# Current_Sensors.net
KiCad netlist of a schematic drawn in Altium Designer
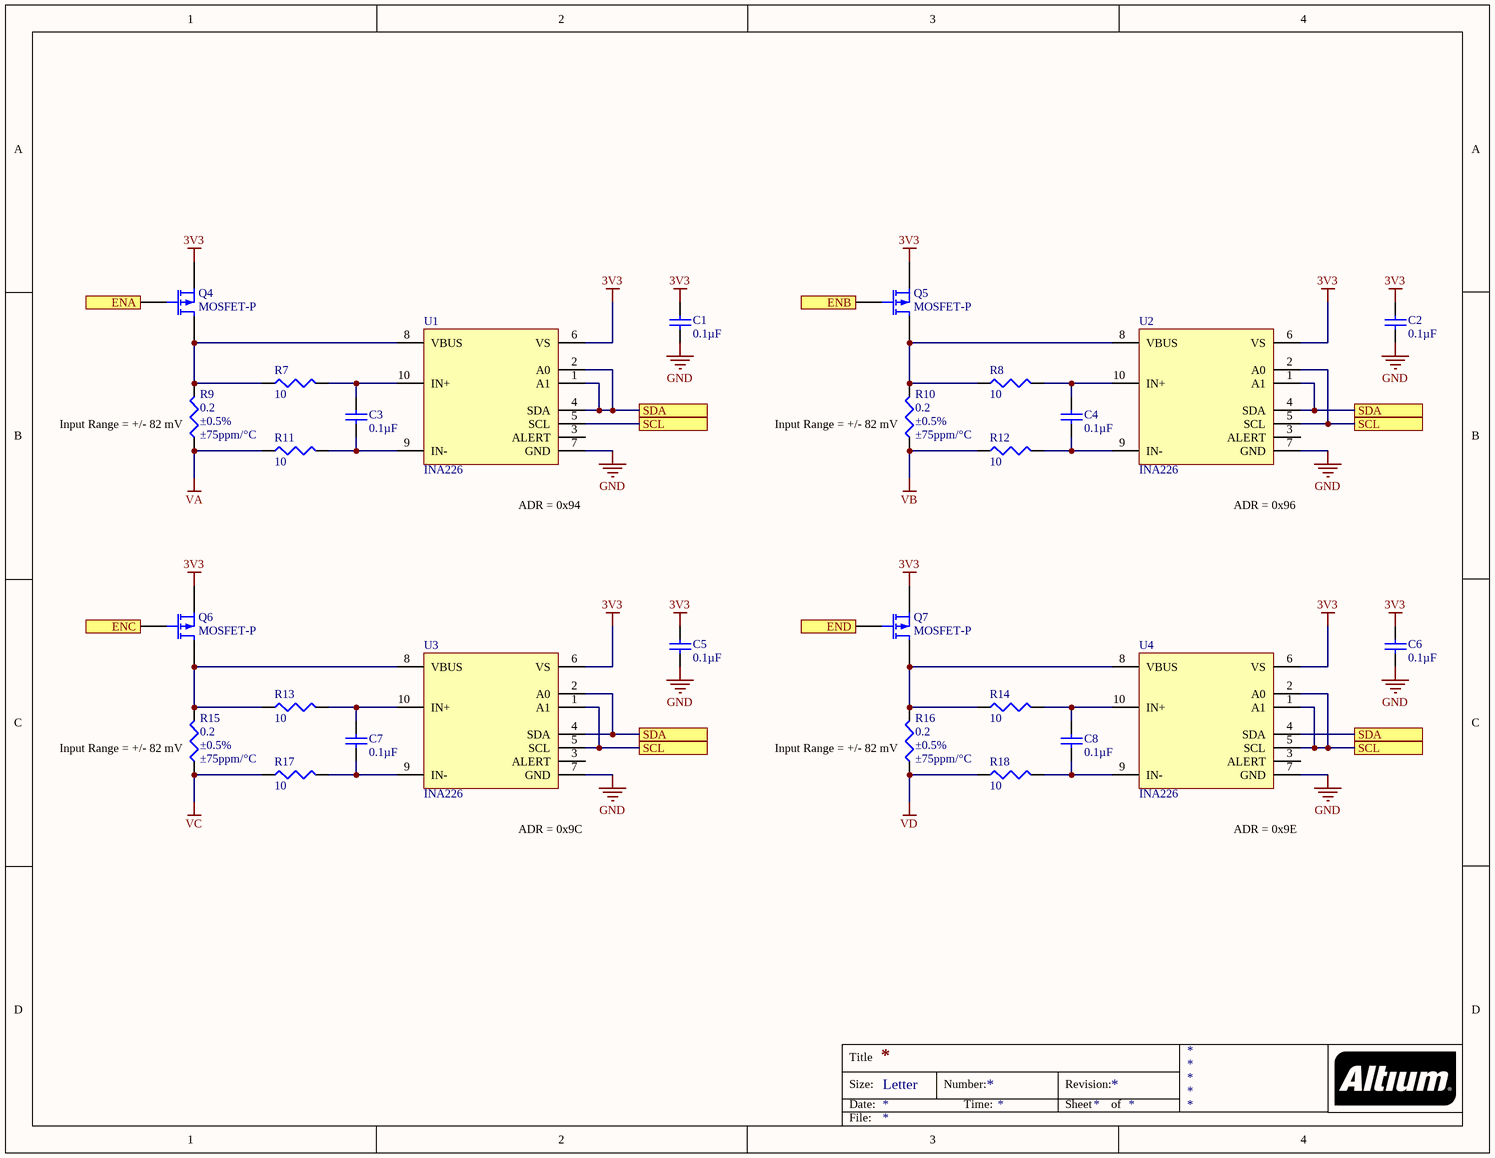
[diagram p0: Current_Sensors.SchDoc]

(export (version "E")
  (design (tool "Eeschema 10.0.6"))
  (components
    (comp (ref "C1")
      (value "0.1µF")
      (footprint "TDK-CGA3E")
      (description "CAP CER 0.1UF 50V X8R 0603")
      (fields
        (field (name "PART NUMBER") "PC-TDK-02273")
        (field (name "MANUFACTURER PART NUMBER") "CGA3E3X8R1H104M080AB")
        (field (name "PUBLISHER") "AlbertaSat")
      )
      (libsource (lib "Database") (part "Cap"))
    )
    (comp (ref "C2")
      (value "0.1µF")
      (footprint "TDK-CGA3E")
      (description "CAP CER 0.1UF 50V X8R 0603")
      (fields
        (field (name "PART NUMBER") "PC-TDK-02273")
        (field (name "MANUFACTURER PART NUMBER") "CGA3E3X8R1H104M080AB")
        (field (name "PUBLISHER") "AlbertaSat")
      )
      (libsource (lib "Database") (part "Cap"))
    )
    (comp (ref "C3")
      (value "0.1µF")
      (footprint "TDK-CGA3E")
      (description "CAP CER 0.1UF 50V X8R 0603")
      (fields
        (field (name "PART NUMBER") "PC-TDK-02272")
        (field (name "MANUFACTURER PART NUMBER") "CGA3E3X8R1H104K080AB")
        (field (name "PUBLISHER") "AlbertaSat")
      )
      (libsource (lib "Database") (part "Cap"))
    )
    (comp (ref "C4")
      (value "0.1µF")
      (footprint "TDK-CGA3E")
      (description "CAP CER 0.1UF 50V X8R 0603")
      (fields
        (field (name "PART NUMBER") "PC-TDK-02272")
        (field (name "MANUFACTURER PART NUMBER") "CGA3E3X8R1H104K080AB")
        (field (name "PUBLISHER") "AlbertaSat")
      )
      (libsource (lib "Database") (part "Cap"))
    )
    (comp (ref "C5")
      (value "0.1µF")
      (footprint "TDK-CGA3E")
      (description "CAP CER 0.1UF 50V X8R 0603")
      (fields
        (field (name "PART NUMBER") "PC-TDK-02273")
        (field (name "MANUFACTURER PART NUMBER") "CGA3E3X8R1H104M080AB")
        (field (name "PUBLISHER") "AlbertaSat")
      )
      (libsource (lib "Database") (part "Cap"))
    )
    (comp (ref "C6")
      (value "0.1µF")
      (footprint "TDK-CGA3E")
      (description "CAP CER 0.1UF 50V X8R 0603")
      (fields
        (field (name "PART NUMBER") "PC-TDK-02273")
        (field (name "MANUFACTURER PART NUMBER") "CGA3E3X8R1H104M080AB")
        (field (name "PUBLISHER") "AlbertaSat")
      )
      (libsource (lib "Database") (part "Cap"))
    )
    (comp (ref "C7")
      (value "0.1µF")
      (footprint "TDK-CGA3E")
      (description "CAP CER 0.1UF 50V X8R 0603")
      (fields
        (field (name "PART NUMBER") "PC-TDK-02272")
        (field (name "MANUFACTURER PART NUMBER") "CGA3E3X8R1H104K080AB")
        (field (name "PUBLISHER") "AlbertaSat")
      )
      (libsource (lib "Database") (part "Cap"))
    )
    (comp (ref "C8")
      (value "0.1µF")
      (footprint "TDK-CGA3E")
      (description "CAP CER 0.1UF 50V X8R 0603")
      (fields
        (field (name "PART NUMBER") "PC-TDK-02272")
        (field (name "MANUFACTURER PART NUMBER") "CGA3E3X8R1H104K080AB")
        (field (name "PUBLISHER") "AlbertaSat")
      )
      (libsource (lib "Database") (part "Cap"))
    )
    (comp (ref "Q4")
      (value "MOSFET-P")
      (footprint "VSH-SO-8L")
      (description "MOSFET P-CH 12V 60A POWERPAKSO-8")
      (fields
        (field (name "PART NUMBER") "PQ-VSH-00264")
        (field (name "MANUFACTURER PART NUMBER") "SQJ411EP-T1_GE3")
        (field (name "PUBLISHER") "AlbertaSat")
      )
      (libsource (lib "Database") (part "MOSFET-P"))
    )
    (comp (ref "Q5")
      (value "MOSFET-P")
      (footprint "VSH-SO-8L")
      (description "MOSFET P-CH 12V 60A POWERPAKSO-8")
      (fields
        (field (name "PART NUMBER") "PQ-VSH-00264")
        (field (name "MANUFACTURER PART NUMBER") "SQJ411EP-T1_GE3")
        (field (name "PUBLISHER") "AlbertaSat")
      )
      (libsource (lib "Database") (part "MOSFET-P"))
    )
    (comp (ref "Q6")
      (value "MOSFET-P")
      (footprint "VSH-SO-8L")
      (description "MOSFET P-CH 12V 60A POWERPAKSO-8")
      (fields
        (field (name "PART NUMBER") "PQ-VSH-00264")
        (field (name "MANUFACTURER PART NUMBER") "SQJ411EP-T1_GE3")
        (field (name "PUBLISHER") "AlbertaSat")
      )
      (libsource (lib "Database") (part "MOSFET-P"))
    )
    (comp (ref "Q7")
      (value "MOSFET-P")
      (footprint "VSH-SO-8L")
      (description "MOSFET P-CH 12V 60A POWERPAKSO-8")
      (fields
        (field (name "PART NUMBER") "PQ-VSH-00264")
        (field (name "MANUFACTURER PART NUMBER") "SQJ411EP-T1_GE3")
        (field (name "PUBLISHER") "AlbertaSat")
      )
      (libsource (lib "Database") (part "MOSFET-P"))
    )
    (comp (ref "R7")
      (value "10")
      (footprint "PANA-ERA2A")
      (description "RES SMD 10 OHM 0.5% 1/16W 0402")
      (fields
        (field (name "PART NUMBER") "13235")
        (field (name "MANUFACTURER PART NUMBER") "ERA-2AKD100X")
        (field (name "PUBLISHER") "Altium Limited")
      )
      (libsource (lib "Database") (part "Res3"))
    )
    (comp (ref "R8")
      (value "10")
      (footprint "PANA-ERA2A")
      (description "RES SMD 10 OHM 0.5% 1/16W 0402")
      (fields
        (field (name "PART NUMBER") "13235")
        (field (name "MANUFACTURER PART NUMBER") "ERA-2AKD100X")
        (field (name "PUBLISHER") "Altium Limited")
      )
      (libsource (lib "Database") (part "Res3"))
    )
    (comp (ref "R9")
      (value "0.2")
      (footprint "VSH-WSL2512")
      (description "Current Sense Resistors - SMD 1watt .2ohms .5% 2512")
      (fields
        (field (name "PART NUMBER") "PR-VSH-00260")
        (field (name "MANUFACTURER PART NUMBER") "WSL2512R2000DEA")
        (field (name "TOLERANCE") "±0.5%")
        (field (name "TEMPERATURE COEFFICIENT") "±75ppm/°C")
        (field (name "PUBLISHER") "AlbertaSat")
      )
      (libsource (lib "Database") (part "Res3"))
    )
    (comp (ref "R10")
      (value "0.2")
      (footprint "VSH-WSL2512")
      (description "Current Sense Resistors - SMD 1watt .2ohms .5% 2512")
      (fields
        (field (name "PART NUMBER") "PR-VSH-00260")
        (field (name "MANUFACTURER PART NUMBER") "WSL2512R2000DEA")
        (field (name "TOLERANCE") "±0.5%")
        (field (name "TEMPERATURE COEFFICIENT") "±75ppm/°C")
        (field (name "PUBLISHER") "AlbertaSat")
      )
      (libsource (lib "Database") (part "Res3"))
    )
    (comp (ref "R11")
      (value "10")
      (footprint "PANA-ERA2A")
      (description "RES SMD 10 OHM 0.5% 1/16W 0402")
      (fields
        (field (name "PART NUMBER") "13235")
        (field (name "MANUFACTURER PART NUMBER") "ERA-2AKD100X")
        (field (name "PUBLISHER") "Altium Limited")
      )
      (libsource (lib "Database") (part "Res3"))
    )
    (comp (ref "R12")
      (value "10")
      (footprint "PANA-ERA2A")
      (description "RES SMD 10 OHM 0.5% 1/16W 0402")
      (fields
        (field (name "PART NUMBER") "13235")
        (field (name "MANUFACTURER PART NUMBER") "ERA-2AKD100X")
        (field (name "PUBLISHER") "Altium Limited")
      )
      (libsource (lib "Database") (part "Res3"))
    )
    (comp (ref "R13")
      (value "10")
      (footprint "PANA-ERA2A")
      (description "RES SMD 10 OHM 0.5% 1/16W 0402")
      (fields
        (field (name "PART NUMBER") "13235")
        (field (name "MANUFACTURER PART NUMBER") "ERA-2AKD100X")
        (field (name "PUBLISHER") "Altium Limited")
      )
      (libsource (lib "Database") (part "Res3"))
    )
    (comp (ref "R14")
      (value "10")
      (footprint "PANA-ERA2A")
      (description "RES SMD 10 OHM 0.5% 1/16W 0402")
      (fields
        (field (name "PART NUMBER") "13235")
        (field (name "MANUFACTURER PART NUMBER") "ERA-2AKD100X")
        (field (name "PUBLISHER") "Altium Limited")
      )
      (libsource (lib "Database") (part "Res3"))
    )
    (comp (ref "R15")
      (value "0.2")
      (footprint "VSH-WSL2512")
      (description "Current Sense Resistors - SMD 1watt .2ohms .5% 2512")
      (fields
        (field (name "PART NUMBER") "PR-VSH-00260")
        (field (name "MANUFACTURER PART NUMBER") "WSL2512R2000DEA")
        (field (name "TOLERANCE") "±0.5%")
        (field (name "TEMPERATURE COEFFICIENT") "±75ppm/°C")
        (field (name "PUBLISHER") "AlbertaSat")
      )
      (libsource (lib "Database") (part "Res3"))
    )
    (comp (ref "R16")
      (value "0.2")
      (footprint "VSH-WSL2512")
      (description "Current Sense Resistors - SMD 1watt .2ohms .5% 2512")
      (fields
        (field (name "PART NUMBER") "PR-VSH-00260")
        (field (name "MANUFACTURER PART NUMBER") "WSL2512R2000DEA")
        (field (name "TOLERANCE") "±0.5%")
        (field (name "TEMPERATURE COEFFICIENT") "±75ppm/°C")
        (field (name "PUBLISHER") "AlbertaSat")
      )
      (libsource (lib "Database") (part "Res3"))
    )
    (comp (ref "R17")
      (value "10")
      (footprint "PANA-ERA2A")
      (description "RES SMD 10 OHM 0.5% 1/16W 0402")
      (fields
        (field (name "PART NUMBER") "13235")
        (field (name "MANUFACTURER PART NUMBER") "ERA-2AKD100X")
        (field (name "PUBLISHER") "Altium Limited")
      )
      (libsource (lib "Database") (part "Res3"))
    )
    (comp (ref "R18")
      (value "10")
      (footprint "PANA-ERA2A")
      (description "RES SMD 10 OHM 0.5% 1/16W 0402")
      (fields
        (field (name "PART NUMBER") "13235")
        (field (name "MANUFACTURER PART NUMBER") "ERA-2AKD100X")
        (field (name "PUBLISHER") "Altium Limited")
      )
      (libsource (lib "Database") (part "Res3"))
    )
    (comp (ref "U1")
      (value "INA226")
      (footprint "TI-DGS")
      (description "IC MONITOR PWR/CURR BIDIR 10MSOP")
      (fields (field (name "PART NUMBER") "19") (field (name "MANUFACTURER PART NUMBER") "INA226AQDGSRQ1"))
      (libsource (lib "Database") (part "INA226AQ"))
    )
    (comp (ref "U2")
      (value "INA226")
      (footprint "TI-DGS")
      (description "IC MONITOR PWR/CURR BIDIR 10MSOP")
      (fields (field (name "PART NUMBER") "19") (field (name "MANUFACTURER PART NUMBER") "INA226AQDGSRQ1"))
      (libsource (lib "Database") (part "INA226AQ"))
    )
    (comp (ref "U3")
      (value "INA226")
      (footprint "TI-DGS")
      (description "IC MONITOR PWR/CURR BIDIR 10MSOP")
      (fields (field (name "PART NUMBER") "19") (field (name "MANUFACTURER PART NUMBER") "INA226AQDGSRQ1"))
      (libsource (lib "Database") (part "INA226AQ"))
    )
    (comp (ref "U4")
      (value "INA226")
      (footprint "TI-DGS")
      (description "IC MONITOR PWR/CURR BIDIR 10MSOP")
      (fields (field (name "PART NUMBER") "19") (field (name "MANUFACTURER PART NUMBER") "INA226AQDGSRQ1"))
      (libsource (lib "Database") (part "INA226AQ"))
    )
  )
  (nets
    (net (code "1") (name "/ENA") (class "Default")
      (node (ref "Q4") (pin "2") (pinfunction "G_2") (pintype "passive"))
    )
    (net (code "2") (name "/ENB") (class "Default")
      (node (ref "Q5") (pin "2") (pinfunction "G_2") (pintype "passive"))
    )
    (net (code "3") (name "/ENC") (class "Default")
      (node (ref "Q6") (pin "2") (pinfunction "G_2") (pintype "passive"))
    )
    (net (code "4") (name "/END") (class "Default")
      (node (ref "Q7") (pin "2") (pinfunction "G_2") (pintype "passive"))
    )
    (net (code "5") (name "/SCL") (class "Default")
      (node (ref "U1") (pin "5") (pinfunction "SCL_5") (pintype "passive"))
      (node (ref "U2") (pin "2") (pinfunction "A0_2") (pintype "passive"))
      (node (ref "U2") (pin "5") (pinfunction "SCL_5") (pintype "passive"))
      (node (ref "U3") (pin "1") (pinfunction "A1_1") (pintype "passive"))
      (node (ref "U3") (pin "5") (pinfunction "SCL_5") (pintype "passive"))
      (node (ref "U4") (pin "1") (pinfunction "A1_1") (pintype "passive"))
      (node (ref "U4") (pin "2") (pinfunction "A0_2") (pintype "passive"))
      (node (ref "U4") (pin "5") (pinfunction "SCL_5") (pintype "passive"))
    )
    (net (code "6") (name "/SDA") (class "Default")
      (node (ref "U1") (pin "1") (pinfunction "A1_1") (pintype "passive"))
      (node (ref "U1") (pin "2") (pinfunction "A0_2") (pintype "passive"))
      (node (ref "U1") (pin "4") (pinfunction "SDA_4") (pintype "passive"))
      (node (ref "U2") (pin "1") (pinfunction "A1_1") (pintype "passive"))
      (node (ref "U2") (pin "4") (pinfunction "SDA_4") (pintype "passive"))
      (node (ref "U3") (pin "2") (pinfunction "A0_2") (pintype "passive"))
      (node (ref "U3") (pin "4") (pinfunction "SDA_4") (pintype "passive"))
      (node (ref "U4") (pin "4") (pinfunction "SDA_4") (pintype "passive"))
    )
    (net (code "7") (name "3V3") (class "Default")
      (node (ref "C1") (pin "2") (pinfunction "2_2") (pintype "passive"))
      (node (ref "C2") (pin "2") (pinfunction "2_2") (pintype "passive"))
      (node (ref "C5") (pin "2") (pinfunction "2_2") (pintype "passive"))
      (node (ref "C6") (pin "2") (pinfunction "2_2") (pintype "passive"))
      (node (ref "Q4") (pin "3") (pinfunction "S_3") (pintype "passive"))
      (node (ref "Q5") (pin "3") (pinfunction "S_3") (pintype "passive"))
      (node (ref "Q6") (pin "3") (pinfunction "S_3") (pintype "passive"))
      (node (ref "Q7") (pin "3") (pinfunction "S_3") (pintype "passive"))
      (node (ref "U1") (pin "6") (pinfunction "VS_6") (pintype "passive"))
      (node (ref "U2") (pin "6") (pinfunction "VS_6") (pintype "passive"))
      (node (ref "U3") (pin "6") (pinfunction "VS_6") (pintype "passive"))
      (node (ref "U4") (pin "6") (pinfunction "VS_6") (pintype "passive"))
    )
    (net (code "8") (name "GND") (class "Default")
      (node (ref "C1") (pin "1") (pinfunction "1_1") (pintype "passive"))
      (node (ref "C2") (pin "1") (pinfunction "1_1") (pintype "passive"))
      (node (ref "C5") (pin "1") (pinfunction "1_1") (pintype "passive"))
      (node (ref "C6") (pin "1") (pinfunction "1_1") (pintype "passive"))
      (node (ref "U1") (pin "7") (pinfunction "GND_7") (pintype "passive"))
      (node (ref "U2") (pin "7") (pinfunction "GND_7") (pintype "passive"))
      (node (ref "U3") (pin "7") (pinfunction "GND_7") (pintype "passive"))
      (node (ref "U4") (pin "7") (pinfunction "GND_7") (pintype "passive"))
    )
    (net (code "9") (name "Net-(Q4-D)") (class "Default")
      (node (ref "Q4") (pin "1") (pinfunction "D_1") (pintype "passive"))
      (node (ref "R7") (pin "1") (pinfunction "1_1") (pintype "passive"))
      (node (ref "R9") (pin "2") (pinfunction "2_2") (pintype "passive"))
      (node (ref "U1") (pin "8") (pinfunction "VBUS_8") (pintype "passive"))
    )
    (net (code "10") (name "Net-(Q5-D)") (class "Default")
      (node (ref "Q5") (pin "1") (pinfunction "D_1") (pintype "passive"))
      (node (ref "R10") (pin "2") (pinfunction "2_2") (pintype "passive"))
      (node (ref "R8") (pin "1") (pinfunction "1_1") (pintype "passive"))
      (node (ref "U2") (pin "8") (pinfunction "VBUS_8") (pintype "passive"))
    )
    (net (code "11") (name "Net-(Q6-D)") (class "Default")
      (node (ref "Q6") (pin "1") (pinfunction "D_1") (pintype "passive"))
      (node (ref "R13") (pin "1") (pinfunction "1_1") (pintype "passive"))
      (node (ref "R15") (pin "2") (pinfunction "2_2") (pintype "passive"))
      (node (ref "U3") (pin "8") (pinfunction "VBUS_8") (pintype "passive"))
    )
    (net (code "12") (name "Net-(Q7-D)") (class "Default")
      (node (ref "Q7") (pin "1") (pinfunction "D_1") (pintype "passive"))
      (node (ref "R14") (pin "1") (pinfunction "1_1") (pintype "passive"))
      (node (ref "R16") (pin "2") (pinfunction "2_2") (pintype "passive"))
      (node (ref "U4") (pin "8") (pinfunction "VBUS_8") (pintype "passive"))
    )
    (net (code "13") (name "Net-(U1-IN+)") (class "Default")
      (node (ref "C3") (pin "2") (pinfunction "2_2") (pintype "passive"))
      (node (ref "R7") (pin "2") (pinfunction "2_2") (pintype "passive"))
      (node (ref "U1") (pin "10") (pinfunction "IN+_10") (pintype "passive"))
    )
    (net (code "14") (name "Net-(U1-IN-)") (class "Default")
      (node (ref "C3") (pin "1") (pinfunction "1_1") (pintype "passive"))
      (node (ref "R11") (pin "2") (pinfunction "2_2") (pintype "passive"))
      (node (ref "U1") (pin "9") (pinfunction "IN-_9") (pintype "passive"))
    )
    (net (code "15") (name "Net-(U2-IN+)") (class "Default")
      (node (ref "C4") (pin "2") (pinfunction "2_2") (pintype "passive"))
      (node (ref "R8") (pin "2") (pinfunction "2_2") (pintype "passive"))
      (node (ref "U2") (pin "10") (pinfunction "IN+_10") (pintype "passive"))
    )
    (net (code "16") (name "Net-(U2-IN-)") (class "Default")
      (node (ref "C4") (pin "1") (pinfunction "1_1") (pintype "passive"))
      (node (ref "R12") (pin "2") (pinfunction "2_2") (pintype "passive"))
      (node (ref "U2") (pin "9") (pinfunction "IN-_9") (pintype "passive"))
    )
    (net (code "17") (name "Net-(U3-IN+)") (class "Default")
      (node (ref "C7") (pin "2") (pinfunction "2_2") (pintype "passive"))
      (node (ref "R13") (pin "2") (pinfunction "2_2") (pintype "passive"))
      (node (ref "U3") (pin "10") (pinfunction "IN+_10") (pintype "passive"))
    )
    (net (code "18") (name "Net-(U3-IN-)") (class "Default")
      (node (ref "C7") (pin "1") (pinfunction "1_1") (pintype "passive"))
      (node (ref "R17") (pin "2") (pinfunction "2_2") (pintype "passive"))
      (node (ref "U3") (pin "9") (pinfunction "IN-_9") (pintype "passive"))
    )
    (net (code "19") (name "Net-(U4-IN+)") (class "Default")
      (node (ref "C8") (pin "2") (pinfunction "2_2") (pintype "passive"))
      (node (ref "R14") (pin "2") (pinfunction "2_2") (pintype "passive"))
      (node (ref "U4") (pin "10") (pinfunction "IN+_10") (pintype "passive"))
    )
    (net (code "20") (name "Net-(U4-IN-)") (class "Default")
      (node (ref "C8") (pin "1") (pinfunction "1_1") (pintype "passive"))
      (node (ref "R18") (pin "2") (pinfunction "2_2") (pintype "passive"))
      (node (ref "U4") (pin "9") (pinfunction "IN-_9") (pintype "passive"))
    )
    (net (code "21") (name "VA") (class "Default")
      (node (ref "R11") (pin "1") (pinfunction "1_1") (pintype "passive"))
      (node (ref "R9") (pin "1") (pinfunction "1_1") (pintype "passive"))
    )
    (net (code "22") (name "VB") (class "Default")
      (node (ref "R10") (pin "1") (pinfunction "1_1") (pintype "passive"))
      (node (ref "R12") (pin "1") (pinfunction "1_1") (pintype "passive"))
    )
    (net (code "23") (name "VC") (class "Default")
      (node (ref "R15") (pin "1") (pinfunction "1_1") (pintype "passive"))
      (node (ref "R17") (pin "1") (pinfunction "1_1") (pintype "passive"))
    )
    (net (code "24") (name "VD") (class "Default")
      (node (ref "R16") (pin "1") (pinfunction "1_1") (pintype "passive"))
      (node (ref "R18") (pin "1") (pinfunction "1_1") (pintype "passive"))
    )
    (net (code "25") (name "unconnected-(U1-ALERT-Pad3)") (class "Default")
      (node (ref "U1") (pin "3") (pinfunction "ALERT_3") (pintype "passive"))
    )
    (net (code "26") (name "unconnected-(U2-ALERT-Pad3)") (class "Default")
      (node (ref "U2") (pin "3") (pinfunction "ALERT_3") (pintype "passive"))
    )
    (net (code "27") (name "unconnected-(U3-ALERT-Pad3)") (class "Default")
      (node (ref "U3") (pin "3") (pinfunction "ALERT_3") (pintype "passive"))
    )
    (net (code "28") (name "unconnected-(U4-ALERT-Pad3)") (class "Default")
      (node (ref "U4") (pin "3") (pinfunction "ALERT_3") (pintype "passive"))
    )
  )
)
